# Fingertip.net
KiCad netlist of a schematic drawn in EAGLE
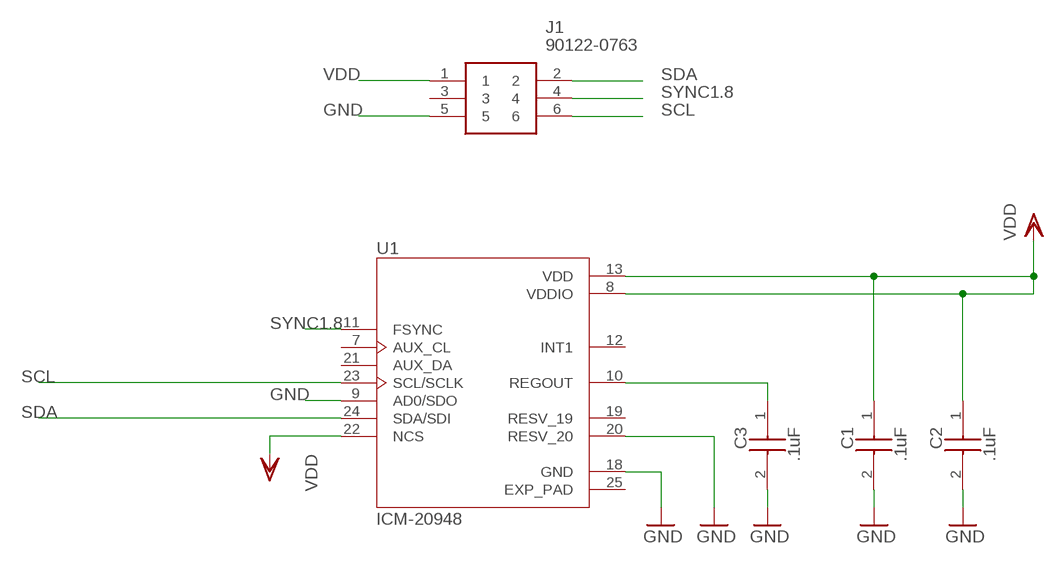
[diagram p0: schematic, sheet 1]

(export (version "E")
  (design (tool "Eeschema 10.0.6"))
  (components
    (comp (ref "C1")
      (value ".1uF")
      (footprint "eagle-import:CAPC2012X88N")
      (fields
        (field (name "MANUFACTURER_PART_NUMBER") "C0805C104K6RACTU")
        (field (name "MOUSER_PART_NUMBER") "80-C0805C104K6R")
      )
      (libsource (lib "eagle-import") (part "C0805C104K6RACTU"))
    )
    (comp (ref "C2")
      (value ".1uF")
      (footprint "eagle-import:CAPC2012X88N")
      (fields
        (field (name "MANUFACTURER_PART_NUMBER") "C0805C104K6RACTU")
        (field (name "MOUSER_PART_NUMBER") "80-C0805C104K6R")
      )
      (libsource (lib "eagle-import") (part "C0805C104K6RACTU"))
    )
    (comp (ref "C3")
      (value ".1uF")
      (footprint "eagle-import:CAPC2012X88N")
      (fields
        (field (name "MANUFACTURER_PART_NUMBER") "C0805C104K6RACTU")
        (field (name "MOUSER_PART_NUMBER") "80-C0805C104K6R")
      )
      (libsource (lib "eagle-import") (part "C0805C104K6RACTU"))
    )
    (comp (ref "J1")
      (value "90122-0763")
      (footprint "eagle-import:SHDR6W90P254_2X3_762X605X684P")
      (fields (field (name "MOUSER_PART_NUMBER") "538-90122-0763"))
      (libsource (lib "eagle-import") (part "90122-0763"))
    )
    (comp (ref "U1")
      (value "ICM-20948")
      (footprint "eagle-import:QFN40P300X300X105-25N")
      (fields (field (name "DIGI-KEY_PART_NUMBER") "1428-1123-1-ND") (field (name "MF") "TDK InvenSense"))
      (libsource (lib "eagle-import") (part "ICM-20948"))
    )
  )
  (nets
    (net (code "1") (name "/EXP_PAD") (class "Default")
      (node (ref "U1") (pin "25") (pinfunction "EXP_PAD_25") (pintype "power_in"))
    )
    (net (code "2") (name "/SCL") (class "Default")
      (node (ref "J1") (pin "6") (pinfunction "6_6") (pintype "bidirectional"))
      (node (ref "U1") (pin "23") (pinfunction "SCL/SCLK_23") (pintype "input"))
    )
    (net (code "3") (name "/SDA") (class "Default")
      (node (ref "J1") (pin "2") (pinfunction "2_2") (pintype "bidirectional"))
      (node (ref "U1") (pin "24") (pinfunction "SDA/SDI_24") (pintype "bidirectional"))
    )
    (net (code "4") (name "/SYNC1.8") (class "Default")
      (node (ref "J1") (pin "4") (pinfunction "4_4") (pintype "bidirectional"))
      (node (ref "U1") (pin "11") (pinfunction "FSYNC_11") (pintype "input"))
    )
    (net (code "5") (name "GND") (class "Default")
      (node (ref "C1") (pin "2") (pinfunction "2_2") (pintype "bidirectional"))
      (node (ref "C2") (pin "2") (pinfunction "2_2") (pintype "bidirectional"))
      (node (ref "C3") (pin "2") (pinfunction "2_2") (pintype "bidirectional"))
      (node (ref "J1") (pin "5") (pinfunction "5_5") (pintype "bidirectional"))
      (node (ref "U1") (pin "18") (pinfunction "GND_18") (pintype "power_in"))
      (node (ref "U1") (pin "20") (pinfunction "RESV_20_20") (pintype "passive"))
      (node (ref "U1") (pin "9") (pinfunction "AD0/SDO_9") (pintype "output"))
    )
    (net (code "6") (name "Net-(U1-REGOUT)") (class "Default")
      (node (ref "C3") (pin "1") (pinfunction "1_1") (pintype "bidirectional"))
      (node (ref "U1") (pin "10") (pinfunction "REGOUT_10") (pintype "output"))
    )
    (net (code "7") (name "VDD") (class "Default")
      (node (ref "C1") (pin "1") (pinfunction "1_1") (pintype "bidirectional"))
      (node (ref "C2") (pin "1") (pinfunction "1_1") (pintype "bidirectional"))
      (node (ref "J1") (pin "1") (pinfunction "1_1") (pintype "bidirectional"))
      (node (ref "U1") (pin "13") (pinfunction "VDD_13") (pintype "power_in"))
      (node (ref "U1") (pin "22") (pinfunction "NCS_22") (pintype "input"))
      (node (ref "U1") (pin "8") (pinfunction "VDDIO_8") (pintype "power_in"))
    )
    (net (code "8") (name "unconnected-(J1-Pad3)") (class "Default")
      (node (ref "J1") (pin "3") (pinfunction "3_3") (pintype "bidirectional"))
    )
    (net (code "9") (name "unconnected-(U1-AUX_CL-Pad7)") (class "Default")
      (node (ref "U1") (pin "7") (pinfunction "AUX_CL_7") (pintype "input"))
    )
    (net (code "10") (name "unconnected-(U1-AUX_DA-Pad21)") (class "Default")
      (node (ref "U1") (pin "21") (pinfunction "AUX_DA_21") (pintype "input"))
    )
    (net (code "11") (name "unconnected-(U1-INT1-Pad12)") (class "Default")
      (node (ref "U1") (pin "12") (pinfunction "INT1_12") (pintype "output"))
    )
    (net (code "12") (name "unconnected-(U1-RESV_19-Pad19)") (class "Default")
      (node (ref "U1") (pin "19") (pinfunction "RESV_19_19") (pintype "passive"))
    )
  )
)
